# breakbeam-interface.net
KiCad netlist of a schematic drawn in Altium Designer
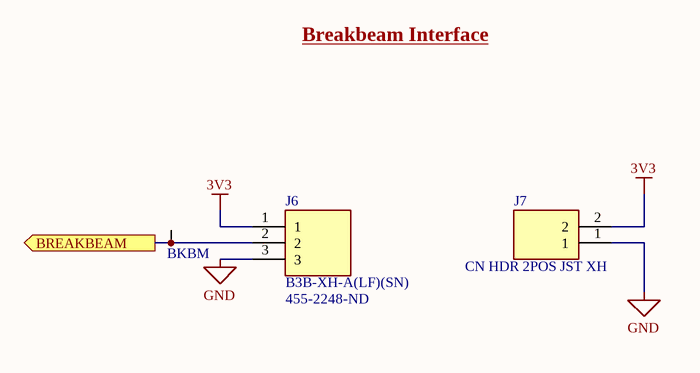
[diagram p0: breakbeam-interface.SchDoc]

(export (version "E")
  (design (tool "Eeschema 10.0.6"))
  (components
    (comp (ref "BKBM")
      (value "Test Point (Via)")
      (footprint "TP")
      (libsource (lib "AltiumLibraries") (part "Test Point (Via)"))
    )
    (comp (ref "J6")
      (value "B3B-XH-A(LF)(SN)")
      (footprint "JST_B3B-XH-A(LF)(SN)")
      (description "Connector Header Through Hole 3 position 0.098 (2.50mm)")
      (fields (field (name "MF") "JST Sales") (field (name "SUPPLIER PART NUMBER 1") "455-2248-ND"))
      (libsource (lib "AltiumLibraries") (part "CN HDR 3POS JST XH"))
    )
    (comp (ref "J7")
      (value "CN HDR 2POS JST XH")
      (footprint "JST_B2B-XH-A(LF)(SN)")
      (description "Connector Header Through Hole 2 position 0.098 _2.50mm_\r\nJST XH")
      (fields (field (name "MP") "B2B-XH-A_LF__SN_") (field (name "MF") "JST Sales"))
      (libsource (lib "AltiumLibraries") (part "CN HDR 2POS JST XH"))
    )
  )
  (nets
    (net (code "1") (name "/BREAKBEAM") (class "Default")
      (node (ref "BKBM") (pin "1") (pinfunction "1_1") (pintype "passive"))
      (node (ref "J6") (pin "2") (pinfunction "2_2") (pintype "passive"))
    )
    (net (code "2") (name "3V3") (class "Default")
      (node (ref "J6") (pin "1") (pinfunction "1_1") (pintype "passive"))
      (node (ref "J7") (pin "2") (pinfunction "2_2") (pintype "passive"))
    )
    (net (code "3") (name "GND") (class "Default")
      (node (ref "J6") (pin "3") (pinfunction "3_3") (pintype "passive"))
      (node (ref "J7") (pin "1") (pinfunction "1_1") (pintype "passive"))
    )
  )
)
